# Main_board.net
KiCad netlist of a schematic drawn in Altium Designer
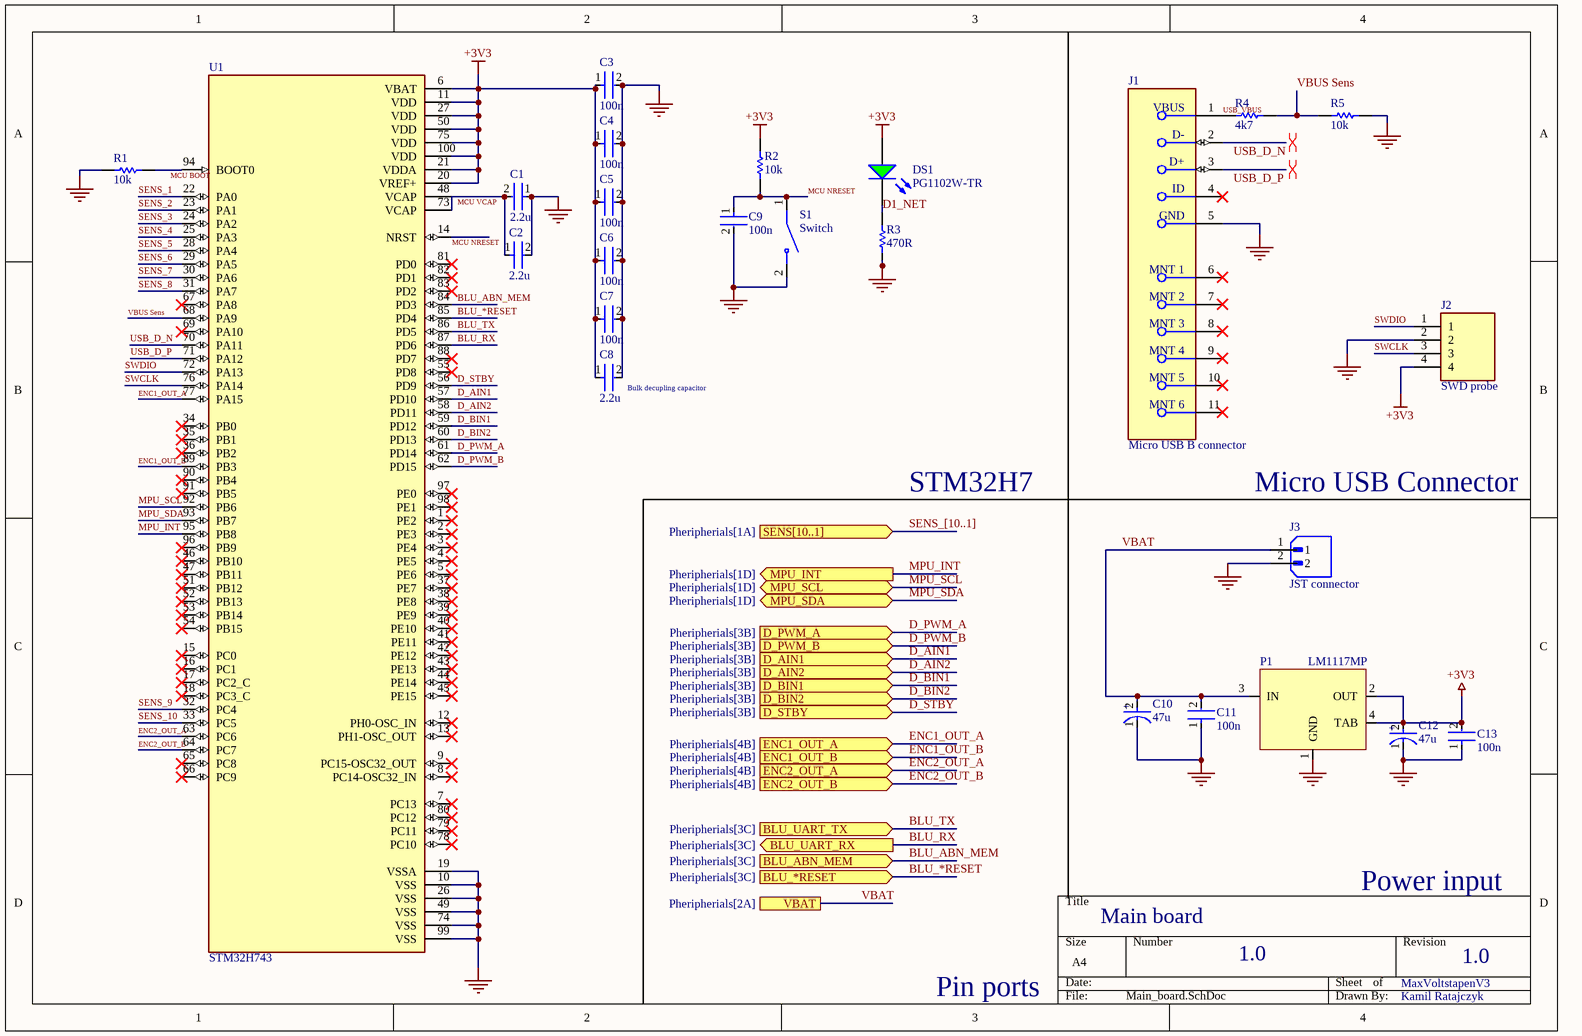
[diagram p0: Main_board.SchDoc]

(export (version "E")
  (design (tool "Eeschema 10.0.6"))
  (components
    (comp (ref "C1")
      (value "2.2u")
      (footprint "FP-CC0805-0_85-MFG")
      (description "CAP CER 0.1UF 16V X7R 0805")
      (fields
        (field (name "MANUFACTURER PART NUMBER") "CC0805KRX7R7BB104")
        (field (name "MANUFACTURER") "Yageo")
      )
      (libsource (lib "Altium Content Vault") (part "11868f565c42a9108669ba33697ecf6"))
    )
    (comp (ref "C2")
      (value "2.2u")
      (footprint "FP-CC0805-0_85-MFG")
      (description "CAP CER 0.1UF 16V X7R 0805")
      (fields
        (field (name "MANUFACTURER PART NUMBER") "CC0805KRX7R7BB104")
        (field (name "MANUFACTURER") "Yageo")
      )
      (libsource (lib "Altium Content Vault") (part "11868f565c42a9108669ba33697ecf6"))
    )
    (comp (ref "C3")
      (value "100n")
      (footprint "FP-CC0805-0_85-MFG")
      (description "CAP CER 0.1UF 16V X7R 0805")
      (fields
        (field (name "MANUFACTURER PART NUMBER") "CC0805KRX7R7BB104")
        (field (name "MANUFACTURER") "Yageo")
      )
      (libsource (lib "Altium Content Vault") (part "11868f565c42a9108669ba33697ecf6"))
    )
    (comp (ref "C4")
      (value "100n")
      (footprint "FP-CC0805-0_85-MFG")
      (description "CAP CER 0.1UF 16V X7R 0805")
      (fields
        (field (name "MANUFACTURER PART NUMBER") "CC0805KRX7R7BB104")
        (field (name "MANUFACTURER") "Yageo")
      )
      (libsource (lib "Altium Content Vault") (part "11868f565c42a9108669ba33697ecf6"))
    )
    (comp (ref "C5")
      (value "100n")
      (footprint "FP-CC0805-0_85-MFG")
      (description "CAP CER 0.1UF 16V X7R 0805")
      (fields
        (field (name "MANUFACTURER PART NUMBER") "CC0805KRX7R7BB104")
        (field (name "MANUFACTURER") "Yageo")
      )
      (libsource (lib "Altium Content Vault") (part "11868f565c42a9108669ba33697ecf6"))
    )
    (comp (ref "C6")
      (value "100n")
      (footprint "FP-CC0805-0_85-MFG")
      (description "CAP CER 0.1UF 16V X7R 0805")
      (fields
        (field (name "MANUFACTURER PART NUMBER") "CC0805KRX7R7BB104")
        (field (name "MANUFACTURER") "Yageo")
      )
      (libsource (lib "Altium Content Vault") (part "11868f565c42a9108669ba33697ecf6"))
    )
    (comp (ref "C7")
      (value "100n")
      (footprint "FP-CC0805-0_85-MFG")
      (description "CAP CER 0.1UF 16V X7R 0805")
      (fields
        (field (name "MANUFACTURER PART NUMBER") "CC0805KRX7R7BB104")
        (field (name "MANUFACTURER") "Yageo")
      )
      (libsource (lib "Altium Content Vault") (part "11868f565c42a9108669ba33697ecf6"))
    )
    (comp (ref "C8")
      (value "2.2u")
      (footprint "FP-CC0805-0_85-MFG")
      (description "CAP CER 0.1UF 16V X7R 0805")
      (fields
        (field (name "MANUFACTURER PART NUMBER") "CC0805KRX7R7BB104")
        (field (name "MANUFACTURER") "Yageo")
      )
      (libsource (lib "Altium Content Vault") (part "11868f565c42a9108669ba33697ecf6"))
    )
    (comp (ref "C9")
      (value "100n")
      (footprint "FP-CC0805-0_85-MFG")
      (description "CAP CER 0.1UF 16V X7R 0805")
      (fields
        (field (name "MANUFACTURER PART NUMBER") "CC0805KRX7R7BB104")
        (field (name "MANUFACTURER") "Yageo")
      )
      (libsource (lib "Altium Content Vault") (part "11868f565c42a9108669ba33697ecf6"))
    )
    (comp (ref "C10")
      (value "47u")
      (footprint "FP-FPD-MFG")
      (description "CAP ALUM 47UF 20% 35V SMD")
      (fields (field (name "TOLERANCE") "20%") (field (name "VOLTAGE") "35V"))
      (libsource (lib "Altium Content Vault") (part "cf48714ba7e38822c1575c7ec0b6d1f"))
    )
    (comp (ref "C11")
      (value "100n")
      (footprint "FP-CC0805-0_85-MFG")
      (description "CAP CER 0.1UF 16V X7R 0805")
      (fields
        (field (name "MANUFACTURER PART NUMBER") "CC0805KRX7R7BB104")
        (field (name "MANUFACTURER") "Yageo")
      )
      (libsource (lib "Altium Content Vault") (part "11868f565c42a9108669ba33697ecf6"))
    )
    (comp (ref "C12")
      (value "47u")
      (footprint "FP-FPD-MFG")
      (description "CAP ALUM 47UF 20% 35V SMD")
      (fields (field (name "TOLERANCE") "20%") (field (name "VOLTAGE") "35V"))
      (libsource (lib "Altium Content Vault") (part "cf48714ba7e38822c1575c7ec0b6d1f"))
    )
    (comp (ref "C13")
      (value "100n")
      (footprint "FP-CC0805-0_85-MFG")
      (description "CAP CER 0.1UF 16V X7R 0805")
      (fields
        (field (name "MANUFACTURER PART NUMBER") "CC0805KRX7R7BB104")
        (field (name "MANUFACTURER") "Yageo")
      )
      (libsource (lib "Altium Content Vault") (part "11868f565c42a9108669ba33697ecf6"))
    )
    (comp (ref "DS1")
      (value "PG1102W-TR")
      (footprint "STEC-1102W_V")
      (description "Green LED, 567 nm, 2.1 V, 30 mA, -30 to 85 degC, 2-Pin SMD, RoHS, Tape and Reel")
      (fields (field (name "MANUFACTURER") "Stanley Electric"))
      (libsource (lib "Altium Content Vault") (part "LED-GREEN-AK-2"))
    )
    (comp (ref "J1")
      (value "Micro USB B connector")
      (footprint "FP-473460001-MFG")
      (description "CONN RCPT USB2.0 MICRO B SMD R/A")
      (fields
        (field (name "OCTOPART") "https://octopart.com/47346-0001-molex-7164928")
        (field (name "MANUFACTURER") "Molex")
      )
      (libsource (lib "Altium Content Vault") (part "53ae1f1d9b557310b43ca686e5bb76a"))
    )
    (comp (ref "J2")
      (value "SWD probe")
      (footprint "TE_1987374-4")
      (description "Pin Connector AMPMODU II PIN HEADER SINGLE ROW 4 POS")
      (fields (field (name "MP") "1987374-4") (field (name "MF") "TE Connectivity"))
      (libsource (lib "Schlib1") (part "1987374-4"))
    )
    (comp (ref "J3")
      (value "JST connector")
      (footprint "JST_B2B-XH-A(LF)(SN)")
      (description "Connector Header Through Hole 2 position 0.098 (2.50mm)")
      (fields (field (name "MF") "JST Sales America Inc.") (field (name "MP") "B2B-XH-A(LF)(SN)"))
      (libsource (lib "Schlib1") (part "B2B-XH-A(LF)(SN)"))
    )
    (comp (ref "P1")
      (value "LM1117MP")
      (footprint "SOT230P700X180-4N")
      (libsource (lib "Schlib1") (part "LM1117MP"))
    )
    (comp (ref "R1")
      (value "10k")
      (footprint "RESC2013X60X35NL10T20")
      (description "Chip Resistor, 10 KOhm, +/- 1%, 0.125 W, -55 to 155 degC, 0805 (2012 Metric), RoHS, Tape and Reel")
      (fields (field (name "MANUFACTURER") "Yageo"))
      (libsource (lib "Altium Content Vault") (part "RES-2"))
    )
    (comp (ref "R2")
      (value "10k")
      (footprint "RESC2013X60X35NL10T20")
      (description "Chip Resistor, 10 KOhm, +/- 1%, 0.125 W, -55 to 155 degC, 0805 (2012 Metric), RoHS, Tape and Reel")
      (fields (field (name "MANUFACTURER") "Yageo"))
      (libsource (lib "Altium Content Vault") (part "RES-2"))
    )
    (comp (ref "R3")
      (value "470R")
      (footprint "RESC2013X60X35NL10T20")
      (description "Chip Resistor, 10 KOhm, +/- 1%, 0.125 W, -55 to 155 degC, 0805 (2012 Metric), RoHS, Tape and Reel")
      (fields (field (name "MANUFACTURER") "Yageo"))
      (libsource (lib "Altium Content Vault") (part "RES-2"))
    )
    (comp (ref "R4")
      (value "4k7")
      (footprint "RESC2013X60X35NL10T20")
      (description "Chip Resistor, 10 KOhm, +/- 1%, 0.125 W, -55 to 155 degC, 0805 (2012 Metric), RoHS, Tape and Reel")
      (fields (field (name "MANUFACTURER") "Yageo"))
      (libsource (lib "Altium Content Vault") (part "RES-2"))
    )
    (comp (ref "R5")
      (value "10k")
      (footprint "RESC2013X60X35NL10T20")
      (description "Chip Resistor, 10 KOhm, +/- 1%, 0.125 W, -55 to 155 degC, 0805 (2012 Metric), RoHS, Tape and Reel")
      (fields (field (name "MANUFACTURER") "Yageo"))
      (libsource (lib "Altium Content Vault") (part "RES-2"))
    )
    (comp (ref "S1")
      (value "Switch")
      (footprint "SW_TS-1088-AR02016")
      (fields (field (name "MF") "Xunpu") (field (name "MP") "TS-1088-AR02016"))
      (libsource (lib "Schlib1") (part "TS-1088-AR02016"))
    )
    (comp (ref "U1")
      (value "STM32H743")
      (footprint "STM32H743")
      (description "ARMÂ® CortexÂ®-M7 STM32H7 Microcontroller IC 32-Bit 480MHz 2MB (2M x 8) FLASH 100-LQFP (14x14)")
      (fields (field (name "MP") "STM32H743VIT6"))
      (libsource (lib "Schlib1") (part "STM32H743"))
    )
  )
  (nets
    (net (code "1") (name "+3V3") (class "Default")
      (node (ref "C12") (pin "2") (pinfunction "A_2") (pintype "passive"))
      (node (ref "C13") (pin "2") (pinfunction "2_2") (pintype "passive"))
      (node (ref "C3") (pin "1") (pinfunction "1_1") (pintype "passive"))
      (node (ref "C4") (pin "1") (pinfunction "1_1") (pintype "passive"))
      (node (ref "C5") (pin "1") (pinfunction "1_1") (pintype "passive"))
      (node (ref "C6") (pin "1") (pinfunction "1_1") (pintype "passive"))
      (node (ref "C7") (pin "1") (pinfunction "1_1") (pintype "passive"))
      (node (ref "C8") (pin "1") (pinfunction "1_1") (pintype "passive"))
      (node (ref "DS1") (pin "1") (pinfunction "A_1") (pintype "passive"))
      (node (ref "J2") (pin "4") (pinfunction "4_4") (pintype "passive"))
      (node (ref "P1") (pin "2") (pinfunction "OUT_2") (pintype "passive"))
      (node (ref "P1") (pin "4") (pinfunction "TAB_4") (pintype "passive"))
      (node (ref "R2") (pin "1") (pinfunction "1_1") (pintype "passive"))
      (node (ref "U1") (pin "100") (pinfunction "VDD_100") (pintype "power_in"))
      (node (ref "U1") (pin "11") (pinfunction "VDD_11") (pintype "power_in"))
      (node (ref "U1") (pin "20") (pinfunction "VREF+_20") (pintype "power_in"))
      (node (ref "U1") (pin "21") (pinfunction "VDDA_21") (pintype "power_in"))
      (node (ref "U1") (pin "27") (pinfunction "VDD_27") (pintype "power_in"))
      (node (ref "U1") (pin "50") (pinfunction "VDD_50") (pintype "power_in"))
      (node (ref "U1") (pin "6") (pinfunction "VBAT_6") (pintype "power_in"))
      (node (ref "U1") (pin "75") (pinfunction "VDD_75") (pintype "power_in"))
    )
    (net (code "2") (name "/BLU_*RESET") (class "Default")
      (node (ref "U1") (pin "85") (pinfunction "PD4_85") (pintype "bidirectional"))
    )
    (net (code "3") (name "/BLU_ABN_MEM") (class "Default")
      (node (ref "U1") (pin "84") (pinfunction "PD3_84") (pintype "bidirectional"))
    )
    (net (code "4") (name "/BLU_RX") (class "Default")
      (node (ref "U1") (pin "87") (pinfunction "PD6_87") (pintype "bidirectional"))
    )
    (net (code "5") (name "/BLU_TX") (class "Default")
      (node (ref "U1") (pin "86") (pinfunction "PD5_86") (pintype "bidirectional"))
    )
    (net (code "6") (name "/D1_NET") (class "Default")
      (node (ref "DS1") (pin "2") (pinfunction "K_2") (pintype "passive"))
      (node (ref "R3") (pin "1") (pinfunction "1_1") (pintype "passive"))
    )
    (net (code "7") (name "/D_AIN1") (class "Default")
      (node (ref "U1") (pin "57") (pinfunction "PD10_57") (pintype "bidirectional"))
    )
    (net (code "8") (name "/D_AIN2") (class "Default")
      (node (ref "U1") (pin "58") (pinfunction "PD11_58") (pintype "bidirectional"))
    )
    (net (code "9") (name "/D_BIN1") (class "Default")
      (node (ref "U1") (pin "59") (pinfunction "PD12_59") (pintype "bidirectional"))
    )
    (net (code "10") (name "/D_BIN2") (class "Default")
      (node (ref "U1") (pin "60") (pinfunction "PD13_60") (pintype "bidirectional"))
    )
    (net (code "11") (name "/D_PWM_A") (class "Default")
      (node (ref "U1") (pin "61") (pinfunction "PD14_61") (pintype "bidirectional"))
    )
    (net (code "12") (name "/D_PWM_B") (class "Default")
      (node (ref "U1") (pin "62") (pinfunction "PD15_62") (pintype "bidirectional"))
    )
    (net (code "13") (name "/D_STBY") (class "Default")
      (node (ref "U1") (pin "56") (pinfunction "PD9_56") (pintype "bidirectional"))
    )
    (net (code "14") (name "/ENC1_OUT_A") (class "Default")
      (node (ref "U1") (pin "77") (pinfunction "PA15_77") (pintype "bidirectional"))
    )
    (net (code "15") (name "/ENC1_OUT_B") (class "Default")
      (node (ref "U1") (pin "89") (pinfunction "PB3_89") (pintype "bidirectional"))
    )
    (net (code "16") (name "/ENC2_OUT_A") (class "Default")
      (node (ref "U1") (pin "63") (pinfunction "PC6_63") (pintype "bidirectional"))
    )
    (net (code "17") (name "/ENC2_OUT_B") (class "Default")
      (node (ref "U1") (pin "64") (pinfunction "PC7_64") (pintype "bidirectional"))
    )
    (net (code "18") (name "/MCU BOOT") (class "Default")
      (node (ref "R1") (pin "2") (pinfunction "2_2") (pintype "passive"))
      (node (ref "U1") (pin "94") (pinfunction "BOOT0_94") (pintype "input"))
    )
    (net (code "19") (name "/MCU NRESET") (class "Default")
      (node (ref "C9") (pin "1") (pinfunction "1_1") (pintype "passive"))
      (node (ref "R2") (pin "2") (pinfunction "2_2") (pintype "passive"))
      (node (ref "S1") (pin "1") (pinfunction "1_1") (pintype "passive"))
      (node (ref "U1") (pin "14") (pinfunction "NRST_14") (pintype "bidirectional"))
    )
    (net (code "20") (name "/MCU VCAP") (class "Default")
      (node (ref "C1") (pin "2") (pinfunction "2_2") (pintype "passive"))
      (node (ref "C2") (pin "1") (pinfunction "1_1") (pintype "passive"))
      (node (ref "U1") (pin "48") (pinfunction "VCAP_48") (pintype "power_in"))
      (node (ref "U1") (pin "73") (pinfunction "VCAP_73") (pintype "power_in"))
    )
    (net (code "21") (name "/MPU_INT") (class "Default")
      (node (ref "U1") (pin "95") (pinfunction "PB8_95") (pintype "bidirectional"))
    )
    (net (code "22") (name "/MPU_SCL") (class "Default")
      (node (ref "U1") (pin "92") (pinfunction "PB6_92") (pintype "bidirectional"))
    )
    (net (code "23") (name "/MPU_SDA") (class "Default")
      (node (ref "U1") (pin "93") (pinfunction "PB7_93") (pintype "bidirectional"))
    )
    (net (code "24") (name "/SENS_1") (class "Default")
      (node (ref "U1") (pin "22") (pinfunction "PA0_22") (pintype "bidirectional"))
    )
    (net (code "25") (name "/SENS_2") (class "Default")
      (node (ref "U1") (pin "23") (pinfunction "PA1_23") (pintype "bidirectional"))
    )
    (net (code "26") (name "/SENS_3") (class "Default")
      (node (ref "U1") (pin "24") (pinfunction "PA2_24") (pintype "bidirectional"))
    )
    (net (code "27") (name "/SENS_4") (class "Default")
      (node (ref "U1") (pin "25") (pinfunction "PA3_25") (pintype "bidirectional"))
    )
    (net (code "28") (name "/SENS_5") (class "Default")
      (node (ref "U1") (pin "28") (pinfunction "PA4_28") (pintype "bidirectional"))
    )
    (net (code "29") (name "/SENS_6") (class "Default")
      (node (ref "U1") (pin "29") (pinfunction "PA5_29") (pintype "bidirectional"))
    )
    (net (code "30") (name "/SENS_7") (class "Default")
      (node (ref "U1") (pin "30") (pinfunction "PA6_30") (pintype "bidirectional"))
    )
    (net (code "31") (name "/SENS_8") (class "Default")
      (node (ref "U1") (pin "31") (pinfunction "PA7_31") (pintype "bidirectional"))
    )
    (net (code "32") (name "/SENS_9") (class "Default")
      (node (ref "U1") (pin "32") (pinfunction "PC4_32") (pintype "bidirectional"))
    )
    (net (code "33") (name "/SENS_10") (class "Default")
      (node (ref "U1") (pin "33") (pinfunction "PC5_33") (pintype "bidirectional"))
    )
    (net (code "35") (name "/SWCLK") (class "Default")
      (node (ref "J2") (pin "3") (pinfunction "3_3") (pintype "passive"))
      (node (ref "U1") (pin "76") (pinfunction "PA14_76") (pintype "bidirectional"))
    )
    (net (code "36") (name "/SWDIO") (class "Default")
      (node (ref "J2") (pin "1") (pinfunction "1_1") (pintype "passive"))
      (node (ref "U1") (pin "72") (pinfunction "PA13_72") (pintype "bidirectional"))
    )
    (net (code "37") (name "/USB_D_N") (class "Default")
      (node (ref "J1") (pin "2") (pinfunction "D-_2") (pintype "bidirectional"))
      (node (ref "U1") (pin "70") (pinfunction "PA11_70") (pintype "bidirectional"))
    )
    (net (code "38") (name "/USB_D_P") (class "Default")
      (node (ref "J1") (pin "3") (pinfunction "D+_3") (pintype "bidirectional"))
      (node (ref "U1") (pin "71") (pinfunction "PA12_71") (pintype "bidirectional"))
    )
    (net (code "39") (name "/USB_VBUS") (class "Default")
      (node (ref "J1") (pin "1") (pinfunction "VBUS_1") (pintype "power_in"))
      (node (ref "R4") (pin "1") (pinfunction "1_1") (pintype "passive"))
    )
    (net (code "40") (name "/VBAT") (class "Default")
      (node (ref "C10") (pin "2") (pinfunction "A_2") (pintype "passive"))
      (node (ref "C11") (pin "2") (pinfunction "2_2") (pintype "passive"))
      (node (ref "J3") (pin "1") (pinfunction "1_1") (pintype "passive"))
      (node (ref "P1") (pin "3") (pinfunction "IN_3") (pintype "passive"))
    )
    (net (code "41") (name "/VBUS Sens") (class "Default")
      (node (ref "R4") (pin "2") (pinfunction "2_2") (pintype "passive"))
      (node (ref "R5") (pin "1") (pinfunction "1_1") (pintype "passive"))
      (node (ref "U1") (pin "68") (pinfunction "PA9_68") (pintype "bidirectional"))
    )
    (net (code "42") (name "GND") (class "Default")
      (node (ref "C1") (pin "1") (pinfunction "1_1") (pintype "passive"))
      (node (ref "C10") (pin "1") (pinfunction "C_1") (pintype "passive"))
      (node (ref "C11") (pin "1") (pinfunction "1_1") (pintype "passive"))
      (node (ref "C12") (pin "1") (pinfunction "C_1") (pintype "passive"))
      (node (ref "C13") (pin "1") (pinfunction "1_1") (pintype "passive"))
      (node (ref "C2") (pin "2") (pinfunction "2_2") (pintype "passive"))
      (node (ref "C3") (pin "2") (pinfunction "2_2") (pintype "passive"))
      (node (ref "C4") (pin "2") (pinfunction "2_2") (pintype "passive"))
      (node (ref "C5") (pin "2") (pinfunction "2_2") (pintype "passive"))
      (node (ref "C6") (pin "2") (pinfunction "2_2") (pintype "passive"))
      (node (ref "C7") (pin "2") (pinfunction "2_2") (pintype "passive"))
      (node (ref "C8") (pin "2") (pinfunction "2_2") (pintype "passive"))
      (node (ref "C9") (pin "2") (pinfunction "2_2") (pintype "passive"))
      (node (ref "J1") (pin "5") (pinfunction "GND_5") (pintype "power_in"))
      (node (ref "J2") (pin "2") (pinfunction "2_2") (pintype "passive"))
      (node (ref "J3") (pin "2") (pinfunction "2_2") (pintype "passive"))
      (node (ref "P1") (pin "1") (pinfunction "GND_1") (pintype "passive"))
      (node (ref "R1") (pin "1") (pinfunction "1_1") (pintype "passive"))
      (node (ref "R3") (pin "2") (pinfunction "2_2") (pintype "passive"))
      (node (ref "R5") (pin "2") (pinfunction "2_2") (pintype "passive"))
      (node (ref "S1") (pin "2") (pinfunction "2_2") (pintype "passive"))
      (node (ref "U1") (pin "10") (pinfunction "VSS_10") (pintype "power_in"))
      (node (ref "U1") (pin "19") (pinfunction "VSSA_19") (pintype "power_in"))
      (node (ref "U1") (pin "26") (pinfunction "VSS_26") (pintype "power_in"))
      (node (ref "U1") (pin "49") (pinfunction "VSS_49") (pintype "power_in"))
      (node (ref "U1") (pin "74") (pinfunction "VSS_74") (pintype "power_in"))
      (node (ref "U1") (pin "99") (pinfunction "VSS_99") (pintype "power_in"))
    )
    (net (code "43") (name "unconnected-(J1-ID-Pad4)") (class "Default")
      (node (ref "J1") (pin "4") (pinfunction "ID_4") (pintype "passive"))
    )
    (net (code "44") (name "unconnected-(J1-MNT_1-Pad6)") (class "Default")
      (node (ref "J1") (pin "6") (pinfunction "MNT_1_6") (pintype "passive+no_connect"))
    )
    (net (code "45") (name "unconnected-(J1-MNT_2-Pad7)") (class "Default")
      (node (ref "J1") (pin "7") (pinfunction "MNT_2_7") (pintype "passive+no_connect"))
    )
    (net (code "46") (name "unconnected-(J1-MNT_3-Pad8)") (class "Default")
      (node (ref "J1") (pin "8") (pinfunction "MNT_3_8") (pintype "passive+no_connect"))
    )
    (net (code "47") (name "unconnected-(J1-MNT_4-Pad9)") (class "Default")
      (node (ref "J1") (pin "9") (pinfunction "MNT_4_9") (pintype "passive+no_connect"))
    )
    (net (code "48") (name "unconnected-(J1-MNT_5-Pad10)") (class "Default")
      (node (ref "J1") (pin "10") (pinfunction "MNT_5_10") (pintype "passive+no_connect"))
    )
    (net (code "49") (name "unconnected-(J1-MNT_6-Pad11)") (class "Default")
      (node (ref "J1") (pin "11") (pinfunction "MNT_6_11") (pintype "passive+no_connect"))
    )
    (net (code "50") (name "unconnected-(U1-PA8-Pad67)") (class "Default")
      (node (ref "U1") (pin "67") (pinfunction "PA8_67") (pintype "bidirectional+no_connect"))
    )
    (net (code "51") (name "unconnected-(U1-PA10-Pad69)") (class "Default")
      (node (ref "U1") (pin "69") (pinfunction "PA10_69") (pintype "bidirectional+no_connect"))
    )
    (net (code "52") (name "unconnected-(U1-PB0-Pad34)") (class "Default")
      (node (ref "U1") (pin "34") (pinfunction "PB0_34") (pintype "bidirectional+no_connect"))
    )
    (net (code "53") (name "unconnected-(U1-PB1-Pad35)") (class "Default")
      (node (ref "U1") (pin "35") (pinfunction "PB1_35") (pintype "bidirectional+no_connect"))
    )
    (net (code "54") (name "unconnected-(U1-PB2-Pad36)") (class "Default")
      (node (ref "U1") (pin "36") (pinfunction "PB2_36") (pintype "bidirectional+no_connect"))
    )
    (net (code "55") (name "unconnected-(U1-PB4-Pad90)") (class "Default")
      (node (ref "U1") (pin "90") (pinfunction "PB4_90") (pintype "bidirectional+no_connect"))
    )
    (net (code "56") (name "unconnected-(U1-PB5-Pad91)") (class "Default")
      (node (ref "U1") (pin "91") (pinfunction "PB5_91") (pintype "bidirectional+no_connect"))
    )
    (net (code "57") (name "unconnected-(U1-PB9-Pad96)") (class "Default")
      (node (ref "U1") (pin "96") (pinfunction "PB9_96") (pintype "bidirectional+no_connect"))
    )
    (net (code "58") (name "unconnected-(U1-PB10-Pad46)") (class "Default")
      (node (ref "U1") (pin "46") (pinfunction "PB10_46") (pintype "bidirectional+no_connect"))
    )
    (net (code "59") (name "unconnected-(U1-PB11-Pad47)") (class "Default")
      (node (ref "U1") (pin "47") (pinfunction "PB11_47") (pintype "bidirectional+no_connect"))
    )
    (net (code "60") (name "unconnected-(U1-PB12-Pad51)") (class "Default")
      (node (ref "U1") (pin "51") (pinfunction "PB12_51") (pintype "bidirectional+no_connect"))
    )
    (net (code "61") (name "unconnected-(U1-PB13-Pad52)") (class "Default")
      (node (ref "U1") (pin "52") (pinfunction "PB13_52") (pintype "bidirectional+no_connect"))
    )
    (net (code "62") (name "unconnected-(U1-PB14-Pad53)") (class "Default")
      (node (ref "U1") (pin "53") (pinfunction "PB14_53") (pintype "bidirectional+no_connect"))
    )
    (net (code "63") (name "unconnected-(U1-PB15-Pad54)") (class "Default")
      (node (ref "U1") (pin "54") (pinfunction "PB15_54") (pintype "bidirectional+no_connect"))
    )
    (net (code "64") (name "unconnected-(U1-PC0-Pad15)") (class "Default")
      (node (ref "U1") (pin "15") (pinfunction "PC0_15") (pintype "bidirectional+no_connect"))
    )
    (net (code "65") (name "unconnected-(U1-PC1-Pad16)") (class "Default")
      (node (ref "U1") (pin "16") (pinfunction "PC1_16") (pintype "bidirectional+no_connect"))
    )
    (net (code "66") (name "unconnected-(U1-PC2_C-Pad17)") (class "Default")
      (node (ref "U1") (pin "17") (pinfunction "PC2_C_17") (pintype "bidirectional+no_connect"))
    )
    (net (code "67") (name "unconnected-(U1-PC3_C-Pad18)") (class "Default")
      (node (ref "U1") (pin "18") (pinfunction "PC3_C_18") (pintype "bidirectional+no_connect"))
    )
    (net (code "68") (name "unconnected-(U1-PC8-Pad65)") (class "Default")
      (node (ref "U1") (pin "65") (pinfunction "PC8_65") (pintype "bidirectional+no_connect"))
    )
    (net (code "69") (name "unconnected-(U1-PC9-Pad66)") (class "Default")
      (node (ref "U1") (pin "66") (pinfunction "PC9_66") (pintype "bidirectional+no_connect"))
    )
    (net (code "70") (name "unconnected-(U1-PC10-Pad78)") (class "Default")
      (node (ref "U1") (pin "78") (pinfunction "PC10_78") (pintype "bidirectional+no_connect"))
    )
    (net (code "71") (name "unconnected-(U1-PC11-Pad79)") (class "Default")
      (node (ref "U1") (pin "79") (pinfunction "PC11_79") (pintype "bidirectional+no_connect"))
    )
    (net (code "72") (name "unconnected-(U1-PC12-Pad80)") (class "Default")
      (node (ref "U1") (pin "80") (pinfunction "PC12_80") (pintype "bidirectional+no_connect"))
    )
    (net (code "73") (name "unconnected-(U1-PC13-Pad7)") (class "Default")
      (node (ref "U1") (pin "7") (pinfunction "PC13_7") (pintype "bidirectional+no_connect"))
    )
    (net (code "74") (name "unconnected-(U1-PC14-OSC32_IN-Pad8)") (class "Default")
      (node (ref "U1") (pin "8") (pinfunction "PC14-OSC32_IN_8") (pintype "bidirectional+no_connect"))
    )
    (net (code "75") (name "unconnected-(U1-PC15-OSC32_OUT-Pad9)") (class "Default")
      (node (ref "U1") (pin "9") (pinfunction "PC15-OSC32_OUT_9") (pintype "bidirectional+no_connect"))
    )
    (net (code "76") (name "unconnected-(U1-PD0-Pad81)") (class "Default")
      (node (ref "U1") (pin "81") (pinfunction "PD0_81") (pintype "bidirectional+no_connect"))
    )
    (net (code "77") (name "unconnected-(U1-PD1-Pad82)") (class "Default")
      (node (ref "U1") (pin "82") (pinfunction "PD1_82") (pintype "bidirectional+no_connect"))
    )
    (net (code "78") (name "unconnected-(U1-PD2-Pad83)") (class "Default")
      (node (ref "U1") (pin "83") (pinfunction "PD2_83") (pintype "bidirectional+no_connect"))
    )
    (net (code "79") (name "unconnected-(U1-PD7-Pad88)") (class "Default")
      (node (ref "U1") (pin "88") (pinfunction "PD7_88") (pintype "bidirectional+no_connect"))
    )
    (net (code "80") (name "unconnected-(U1-PD8-Pad55)") (class "Default")
      (node (ref "U1") (pin "55") (pinfunction "PD8_55") (pintype "bidirectional+no_connect"))
    )
    (net (code "81") (name "unconnected-(U1-PE0-Pad97)") (class "Default")
      (node (ref "U1") (pin "97") (pinfunction "PE0_97") (pintype "bidirectional+no_connect"))
    )
    (net (code "82") (name "unconnected-(U1-PE1-Pad98)") (class "Default")
      (node (ref "U1") (pin "98") (pinfunction "PE1_98") (pintype "bidirectional+no_connect"))
    )
    (net (code "83") (name "unconnected-(U1-PE2-Pad1)") (class "Default")
      (node (ref "U1") (pin "1") (pinfunction "PE2_1") (pintype "bidirectional+no_connect"))
    )
    (net (code "84") (name "unconnected-(U1-PE3-Pad2)") (class "Default")
      (node (ref "U1") (pin "2") (pinfunction "PE3_2") (pintype "bidirectional+no_connect"))
    )
    (net (code "85") (name "unconnected-(U1-PE4-Pad3)") (class "Default")
      (node (ref "U1") (pin "3") (pinfunction "PE4_3") (pintype "bidirectional+no_connect"))
    )
    (net (code "86") (name "unconnected-(U1-PE5-Pad4)") (class "Default")
      (node (ref "U1") (pin "4") (pinfunction "PE5_4") (pintype "bidirectional+no_connect"))
    )
    (net (code "87") (name "unconnected-(U1-PE6-Pad5)") (class "Default")
      (node (ref "U1") (pin "5") (pinfunction "PE6_5") (pintype "bidirectional+no_connect"))
    )
    (net (code "88") (name "unconnected-(U1-PE7-Pad37)") (class "Default")
      (node (ref "U1") (pin "37") (pinfunction "PE7_37") (pintype "bidirectional+no_connect"))
    )
    (net (code "89") (name "unconnected-(U1-PE8-Pad38)") (class "Default")
      (node (ref "U1") (pin "38") (pinfunction "PE8_38") (pintype "bidirectional+no_connect"))
    )
    (net (code "90") (name "unconnected-(U1-PE9-Pad39)") (class "Default")
      (node (ref "U1") (pin "39") (pinfunction "PE9_39") (pintype "bidirectional+no_connect"))
    )
    (net (code "91") (name "unconnected-(U1-PE10-Pad40)") (class "Default")
      (node (ref "U1") (pin "40") (pinfunction "PE10_40") (pintype "bidirectional+no_connect"))
    )
    (net (code "92") (name "unconnected-(U1-PE11-Pad41)") (class "Default")
      (node (ref "U1") (pin "41") (pinfunction "PE11_41") (pintype "bidirectional+no_connect"))
    )
    (net (code "93") (name "unconnected-(U1-PE12-Pad42)") (class "Default")
      (node (ref "U1") (pin "42") (pinfunction "PE12_42") (pintype "bidirectional+no_connect"))
    )
    (net (code "94") (name "unconnected-(U1-PE13-Pad43)") (class "Default")
      (node (ref "U1") (pin "43") (pinfunction "PE13_43") (pintype "bidirectional+no_connect"))
    )
    (net (code "95") (name "unconnected-(U1-PE14-Pad44)") (class "Default")
      (node (ref "U1") (pin "44") (pinfunction "PE14_44") (pintype "bidirectional+no_connect"))
    )
    (net (code "96") (name "unconnected-(U1-PE15-Pad45)") (class "Default")
      (node (ref "U1") (pin "45") (pinfunction "PE15_45") (pintype "bidirectional+no_connect"))
    )
    (net (code "97") (name "unconnected-(U1-PH0-OSC_IN-Pad12)") (class "Default")
      (node (ref "U1") (pin "12") (pinfunction "PH0-OSC_IN_12") (pintype "bidirectional+no_connect"))
    )
    (net (code "98") (name "unconnected-(U1-PH1-OSC_OUT-Pad13)") (class "Default")
      (node (ref "U1") (pin "13") (pinfunction "PH1-OSC_OUT_13") (pintype "bidirectional+no_connect"))
    )
  )
)
